# ccam.net
KiCad netlist of a schematic drawn in EAGLE
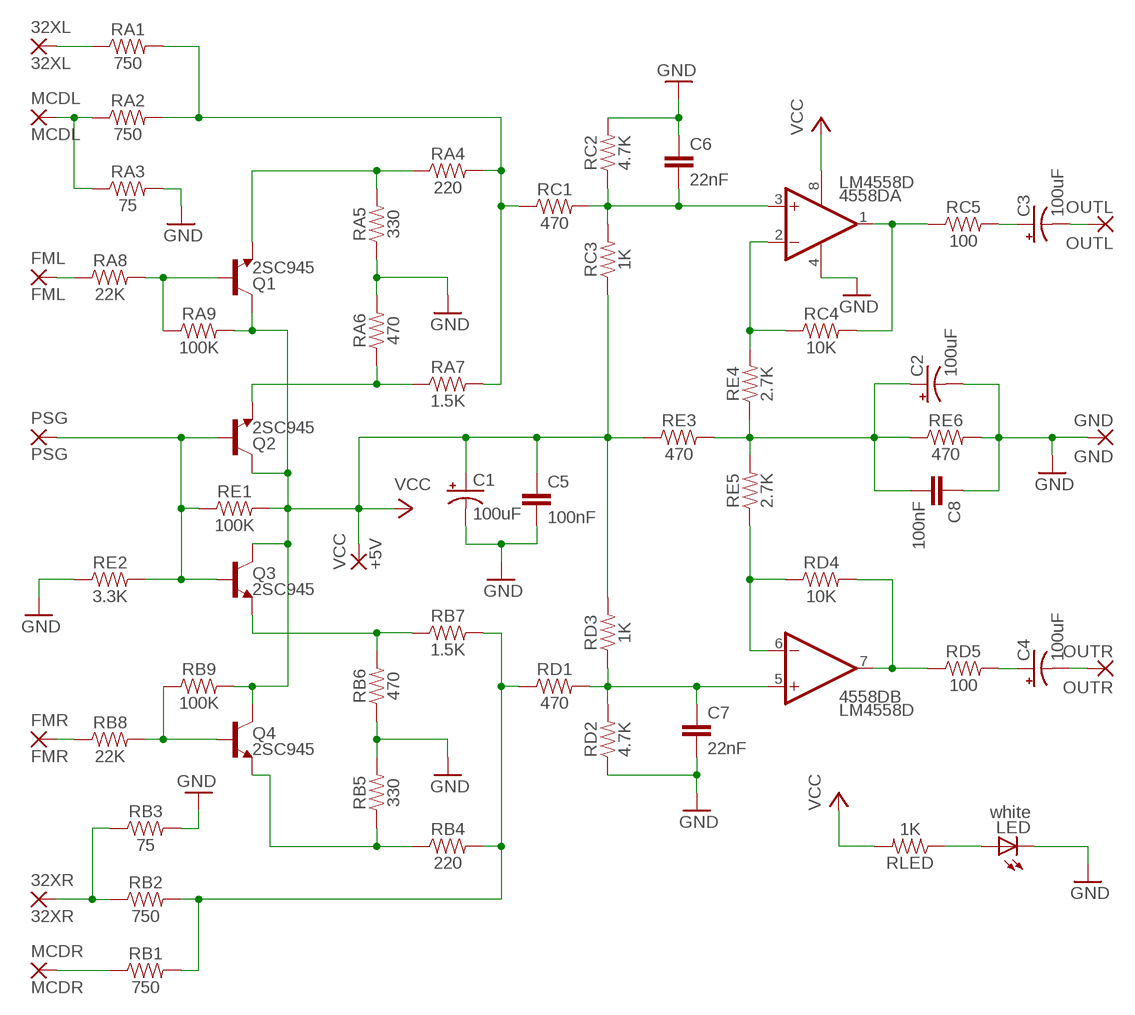
[diagram p0: schematic, sheet 1]

(export (version "E")
  (design (tool "Eeschema 10.0.6"))
  (components
    (comp (ref "32XL")
      (value "32XL")
      (footprint "eagle-import:SMD1,27-2,54")
      (libsource (lib "eagle-import") (part "SMD2"))
    )
    (comp (ref "32XR")
      (value "32XR")
      (footprint "eagle-import:SMD1,27-2,54")
      (libsource (lib "eagle-import") (part "SMD2"))
    )
    (comp (ref "4558D")
      (value "LM4558D")
      (footprint "eagle-import:SO08")
      (libsource (lib "eagle-import") (part "4558DLM"))
    )
    (comp (ref "C1")
      (value "100uF")
      (footprint "eagle-import:EIA6032-NOM")
      (libsource (lib "eagle-import") (part "10UF-POLAR-EIA6032-25V-10%"))
    )
    (comp (ref "C2")
      (value "100uF")
      (footprint "eagle-import:EIA6032-NOM")
      (libsource (lib "eagle-import") (part "10UF-POLAR-EIA6032-25V-10%"))
    )
    (comp (ref "C3")
      (value "100uF")
      (footprint "eagle-import:EIA6032-NOM")
      (libsource (lib "eagle-import") (part "10UF-POLAR-EIA6032-25V-10%"))
    )
    (comp (ref "C4")
      (value "100uF")
      (footprint "eagle-import:EIA6032-NOM")
      (libsource (lib "eagle-import") (part "10UF-POLAR-EIA6032-25V-10%"))
    )
    (comp (ref "C5")
      (value "100nF")
      (footprint "eagle-import:0805")
      (libsource (lib "eagle-import") (part "1.0UF-0805-25V-(+80/-20%)"))
    )
    (comp (ref "C6")
      (value "22nF")
      (footprint "eagle-import:0805")
      (libsource (lib "eagle-import") (part "1.0UF-0805-25V-(+80/-20%)"))
    )
    (comp (ref "C7")
      (value "22nF")
      (footprint "eagle-import:0805")
      (libsource (lib "eagle-import") (part "1.0UF-0805-25V-(+80/-20%)"))
    )
    (comp (ref "C8")
      (value "100nF")
      (footprint "eagle-import:0805")
      (libsource (lib "eagle-import") (part "1.0UF-0805-25V-(+80/-20%)"))
    )
    (comp (ref "FML")
      (value "FML")
      (footprint "eagle-import:SMD1,27-2,54")
      (libsource (lib "eagle-import") (part "SMD2"))
    )
    (comp (ref "FMR")
      (value "FMR")
      (footprint "eagle-import:SMD1,27-2,54")
      (libsource (lib "eagle-import") (part "SMD2"))
    )
    (comp (ref "GND")
      (value "GND")
      (footprint "eagle-import:SMD1,27-2,54")
      (libsource (lib "eagle-import") (part "SMD2"))
    )
    (comp (ref "LED")
      (value "white")
      (footprint "eagle-import:CHIP-LED0805")
      (libsource (lib "eagle-import") (part "LEDCHIP-LED0805"))
    )
    (comp (ref "MCDL")
      (value "MCDL")
      (footprint "eagle-import:SMD1,27-2,54")
      (libsource (lib "eagle-import") (part "SMD2"))
    )
    (comp (ref "MCDR")
      (value "MCDR")
      (footprint "eagle-import:SMD1,27-2,54")
      (libsource (lib "eagle-import") (part "SMD2"))
    )
    (comp (ref "OUTL")
      (value "OUTL")
      (footprint "eagle-import:SMD1,27-2,54")
      (libsource (lib "eagle-import") (part "SMD2"))
    )
    (comp (ref "OUTR")
      (value "OUTR")
      (footprint "eagle-import:SMD1,27-2,54")
      (libsource (lib "eagle-import") (part "SMD2"))
    )
    (comp (ref "PSG")
      (value "PSG")
      (footprint "eagle-import:SMD1,27-2,54")
      (libsource (lib "eagle-import") (part "SMD2"))
    )
    (comp (ref "Q1")
      (value "2SC945")
      (footprint "eagle-import:SOT23-3")
      (libsource (lib "eagle-import") (part "TRANS_NPN-MMBT2222AL"))
    )
    (comp (ref "Q2")
      (value "2SC945")
      (footprint "eagle-import:SOT23-3")
      (libsource (lib "eagle-import") (part "TRANS_NPN-MMBT2222AL"))
    )
    (comp (ref "Q3")
      (value "2SC945")
      (footprint "eagle-import:SOT23-3")
      (libsource (lib "eagle-import") (part "TRANS_NPN-MMBT2222AL"))
    )
    (comp (ref "Q4")
      (value "2SC945")
      (footprint "eagle-import:SOT23-3")
      (libsource (lib "eagle-import") (part "TRANS_NPN-MMBT2222AL"))
    )
    (comp (ref "RA1")
      (value "750")
      (footprint "eagle-import:0805")
      (libsource (lib "eagle-import") (part "0.22OHM-0805-1/4W-1%"))
    )
    (comp (ref "RA2")
      (value "750")
      (footprint "eagle-import:0805")
      (libsource (lib "eagle-import") (part "0.22OHM-0805-1/4W-1%"))
    )
    (comp (ref "RA3")
      (value "75")
      (footprint "eagle-import:0805")
      (libsource (lib "eagle-import") (part "0.22OHM-0805-1/4W-1%"))
    )
    (comp (ref "RA4")
      (value "220")
      (footprint "eagle-import:0805")
      (libsource (lib "eagle-import") (part "0.22OHM-0805-1/4W-1%"))
    )
    (comp (ref "RA5")
      (value "330")
      (footprint "eagle-import:0805")
      (libsource (lib "eagle-import") (part "0.22OHM-0805-1/4W-1%"))
    )
    (comp (ref "RA6")
      (value "470")
      (footprint "eagle-import:0805")
      (libsource (lib "eagle-import") (part "0.22OHM-0805-1/4W-1%"))
    )
    (comp (ref "RA7")
      (value "1.5K")
      (footprint "eagle-import:0805")
      (libsource (lib "eagle-import") (part "0.22OHM-0805-1/4W-1%"))
    )
    (comp (ref "RA8")
      (value "22K")
      (footprint "eagle-import:0805")
      (libsource (lib "eagle-import") (part "0.22OHM-0805-1/4W-1%"))
    )
    (comp (ref "RA9")
      (value "100K")
      (footprint "eagle-import:0805")
      (libsource (lib "eagle-import") (part "0.22OHM-0805-1/4W-1%"))
    )
    (comp (ref "RB1")
      (value "750")
      (footprint "eagle-import:0805")
      (libsource (lib "eagle-import") (part "0.22OHM-0805-1/4W-1%"))
    )
    (comp (ref "RB2")
      (value "750")
      (footprint "eagle-import:0805")
      (libsource (lib "eagle-import") (part "0.22OHM-0805-1/4W-1%"))
    )
    (comp (ref "RB3")
      (value "75")
      (footprint "eagle-import:0805")
      (libsource (lib "eagle-import") (part "0.22OHM-0805-1/4W-1%"))
    )
    (comp (ref "RB4")
      (value "220")
      (footprint "eagle-import:0805")
      (libsource (lib "eagle-import") (part "0.22OHM-0805-1/4W-1%"))
    )
    (comp (ref "RB5")
      (value "330")
      (footprint "eagle-import:0805")
      (libsource (lib "eagle-import") (part "0.22OHM-0805-1/4W-1%"))
    )
    (comp (ref "RB6")
      (value "470")
      (footprint "eagle-import:0805")
      (libsource (lib "eagle-import") (part "0.22OHM-0805-1/4W-1%"))
    )
    (comp (ref "RB7")
      (value "1.5K")
      (footprint "eagle-import:0805")
      (libsource (lib "eagle-import") (part "0.22OHM-0805-1/4W-1%"))
    )
    (comp (ref "RB8")
      (value "22K")
      (footprint "eagle-import:0805")
      (libsource (lib "eagle-import") (part "0.22OHM-0805-1/4W-1%"))
    )
    (comp (ref "RB9")
      (value "100K")
      (footprint "eagle-import:0805")
      (libsource (lib "eagle-import") (part "0.22OHM-0805-1/4W-1%"))
    )
    (comp (ref "RC1")
      (value "470")
      (footprint "eagle-import:0805")
      (libsource (lib "eagle-import") (part "0.22OHM-0805-1/4W-1%"))
    )
    (comp (ref "RC2")
      (value "4.7K")
      (footprint "eagle-import:0805")
      (libsource (lib "eagle-import") (part "0.22OHM-0805-1/4W-1%"))
    )
    (comp (ref "RC3")
      (value "1K")
      (footprint "eagle-import:0805")
      (libsource (lib "eagle-import") (part "0.22OHM-0805-1/4W-1%"))
    )
    (comp (ref "RC4")
      (value "10K")
      (footprint "eagle-import:0805")
      (libsource (lib "eagle-import") (part "0.22OHM-0805-1/4W-1%"))
    )
    (comp (ref "RC5")
      (value "100")
      (footprint "eagle-import:0805")
      (libsource (lib "eagle-import") (part "0.22OHM-0805-1/4W-1%"))
    )
    (comp (ref "RD1")
      (value "470")
      (footprint "eagle-import:0805")
      (libsource (lib "eagle-import") (part "0.22OHM-0805-1/4W-1%"))
    )
    (comp (ref "RD2")
      (value "4.7K")
      (footprint "eagle-import:0805")
      (libsource (lib "eagle-import") (part "0.22OHM-0805-1/4W-1%"))
    )
    (comp (ref "RD3")
      (value "1K")
      (footprint "eagle-import:0805")
      (libsource (lib "eagle-import") (part "0.22OHM-0805-1/4W-1%"))
    )
    (comp (ref "RD4")
      (value "10K")
      (footprint "eagle-import:0805")
      (libsource (lib "eagle-import") (part "0.22OHM-0805-1/4W-1%"))
    )
    (comp (ref "RD5")
      (value "100")
      (footprint "eagle-import:0805")
      (libsource (lib "eagle-import") (part "0.22OHM-0805-1/4W-1%"))
    )
    (comp (ref "RE1")
      (value "100K")
      (footprint "eagle-import:0805")
      (libsource (lib "eagle-import") (part "0.22OHM-0805-1/4W-1%"))
    )
    (comp (ref "RE2")
      (value "3.3K")
      (footprint "eagle-import:0805")
      (libsource (lib "eagle-import") (part "0.22OHM-0805-1/4W-1%"))
    )
    (comp (ref "RE3")
      (value "470")
      (footprint "eagle-import:0805")
      (libsource (lib "eagle-import") (part "0.22OHM-0805-1/4W-1%"))
    )
    (comp (ref "RE4")
      (value "2.7K")
      (footprint "eagle-import:0805")
      (libsource (lib "eagle-import") (part "0.22OHM-0805-1/4W-1%"))
    )
    (comp (ref "RE5")
      (value "2.7K")
      (footprint "eagle-import:0805")
      (libsource (lib "eagle-import") (part "0.22OHM-0805-1/4W-1%"))
    )
    (comp (ref "RE6")
      (value "470")
      (footprint "eagle-import:0805")
      (libsource (lib "eagle-import") (part "0.22OHM-0805-1/4W-1%"))
    )
    (comp (ref "RLED")
      (value "1K")
      (footprint "eagle-import:0805")
      (libsource (lib "eagle-import") (part "0.22OHM-0805-1/4W-1%"))
    )
    (comp (ref "VCC")
      (value "+5V")
      (footprint "eagle-import:SMD1,27-2,54")
      (libsource (lib "eagle-import") (part "SMD2"))
    )
  )
  (nets
    (net (code "1") (name "GND") (class "Default")
      (node (ref "4558D") (pin "4") (pinfunction "V-_4") (pintype "power_in"))
      (node (ref "C1") (pin "C") (pinfunction "-_C") (pintype "passive"))
      (node (ref "C2") (pin "C") (pinfunction "-_C") (pintype "passive"))
      (node (ref "C5") (pin "2") (pinfunction "2_2") (pintype "passive"))
      (node (ref "C6") (pin "1") (pinfunction "1_1") (pintype "passive"))
      (node (ref "C7") (pin "2") (pinfunction "2_2") (pintype "passive"))
      (node (ref "C8") (pin "1") (pinfunction "1_1") (pintype "passive"))
      (node (ref "GND") (pin "1") (pinfunction "P_1") (pintype "passive"))
      (node (ref "LED") (pin "C") (pinfunction "C_C") (pintype "passive"))
      (node (ref "RA3") (pin "2") (pinfunction "2_2") (pintype "passive"))
      (node (ref "RA5") (pin "1") (pinfunction "1_1") (pintype "passive"))
      (node (ref "RA6") (pin "2") (pinfunction "2_2") (pintype "passive"))
      (node (ref "RB3") (pin "2") (pinfunction "2_2") (pintype "passive"))
      (node (ref "RB5") (pin "2") (pinfunction "2_2") (pintype "passive"))
      (node (ref "RB6") (pin "1") (pinfunction "1_1") (pintype "passive"))
      (node (ref "RC2") (pin "2") (pinfunction "2_2") (pintype "passive"))
      (node (ref "RD2") (pin "1") (pinfunction "1_1") (pintype "passive"))
      (node (ref "RE2") (pin "1") (pinfunction "1_1") (pintype "passive"))
      (node (ref "RE6") (pin "2") (pinfunction "2_2") (pintype "passive"))
    )
    (net (code "2") (name "Net-(32XL-P)") (class "Default")
      (node (ref "32XL") (pin "1") (pinfunction "P_1") (pintype "passive"))
      (node (ref "RA1") (pin "1") (pinfunction "1_1") (pintype "passive"))
    )
    (net (code "3") (name "Net-(32XR-P)") (class "Default")
      (node (ref "32XR") (pin "1") (pinfunction "P_1") (pintype "passive"))
      (node (ref "RB2") (pin "1") (pinfunction "1_1") (pintype "passive"))
      (node (ref "RB3") (pin "1") (pinfunction "1_1") (pintype "passive"))
    )
    (net (code "4") (name "Net-(4558DA-+IN)") (class "Default")
      (node (ref "4558D") (pin "3") (pinfunction "+IN_3") (pintype "input"))
      (node (ref "C6") (pin "2") (pinfunction "2_2") (pintype "passive"))
      (node (ref "RC1") (pin "2") (pinfunction "2_2") (pintype "passive"))
      (node (ref "RC2") (pin "1") (pinfunction "1_1") (pintype "passive"))
      (node (ref "RC3") (pin "2") (pinfunction "2_2") (pintype "passive"))
    )
    (net (code "5") (name "Net-(4558DA--IN)") (class "Default")
      (node (ref "4558D") (pin "2") (pinfunction "-IN_2") (pintype "input"))
      (node (ref "RC4") (pin "1") (pinfunction "1_1") (pintype "passive"))
      (node (ref "RE4") (pin "2") (pinfunction "2_2") (pintype "passive"))
    )
    (net (code "6") (name "Net-(4558DA-OUT)") (class "Default")
      (node (ref "4558D") (pin "1") (pinfunction "OUT_1") (pintype "output"))
      (node (ref "RC4") (pin "2") (pinfunction "2_2") (pintype "passive"))
      (node (ref "RC5") (pin "1") (pinfunction "1_1") (pintype "passive"))
    )
    (net (code "7") (name "Net-(4558DB-+IN)") (class "Default")
      (node (ref "4558D") (pin "5") (pinfunction "+IN_5") (pintype "input"))
      (node (ref "C7") (pin "1") (pinfunction "1_1") (pintype "passive"))
      (node (ref "RD1") (pin "2") (pinfunction "2_2") (pintype "passive"))
      (node (ref "RD2") (pin "2") (pinfunction "2_2") (pintype "passive"))
      (node (ref "RD3") (pin "1") (pinfunction "1_1") (pintype "passive"))
    )
    (net (code "8") (name "Net-(4558DB--IN)") (class "Default")
      (node (ref "4558D") (pin "6") (pinfunction "-IN_6") (pintype "input"))
      (node (ref "RD4") (pin "1") (pinfunction "1_1") (pintype "passive"))
      (node (ref "RE5") (pin "1") (pinfunction "1_1") (pintype "passive"))
    )
    (net (code "9") (name "Net-(4558DB-OUT)") (class "Default")
      (node (ref "4558D") (pin "7") (pinfunction "OUT_7") (pintype "output"))
      (node (ref "RD4") (pin "2") (pinfunction "2_2") (pintype "passive"))
      (node (ref "RD5") (pin "1") (pinfunction "1_1") (pintype "passive"))
    )
    (net (code "10") (name "Net-(C2-+)") (class "Default")
      (node (ref "C2") (pin "A") (pinfunction "+_A") (pintype "passive"))
      (node (ref "C8") (pin "2") (pinfunction "2_2") (pintype "passive"))
      (node (ref "RE3") (pin "2") (pinfunction "2_2") (pintype "passive"))
      (node (ref "RE4") (pin "1") (pinfunction "1_1") (pintype "passive"))
      (node (ref "RE5") (pin "2") (pinfunction "2_2") (pintype "passive"))
      (node (ref "RE6") (pin "1") (pinfunction "1_1") (pintype "passive"))
    )
    (net (code "11") (name "Net-(C3-+)") (class "Default")
      (node (ref "C3") (pin "A") (pinfunction "+_A") (pintype "passive"))
      (node (ref "RC5") (pin "2") (pinfunction "2_2") (pintype "passive"))
    )
    (net (code "12") (name "Net-(C3--)") (class "Default")
      (node (ref "C3") (pin "C") (pinfunction "-_C") (pintype "passive"))
      (node (ref "OUTL") (pin "1") (pinfunction "P_1") (pintype "passive"))
    )
    (net (code "13") (name "Net-(C4-+)") (class "Default")
      (node (ref "C4") (pin "A") (pinfunction "+_A") (pintype "passive"))
      (node (ref "RD5") (pin "2") (pinfunction "2_2") (pintype "passive"))
    )
    (net (code "14") (name "Net-(C4--)") (class "Default")
      (node (ref "C4") (pin "C") (pinfunction "-_C") (pintype "passive"))
      (node (ref "OUTR") (pin "1") (pinfunction "P_1") (pintype "passive"))
    )
    (net (code "15") (name "Net-(FML-P)") (class "Default")
      (node (ref "FML") (pin "1") (pinfunction "P_1") (pintype "passive"))
      (node (ref "RA8") (pin "1") (pinfunction "1_1") (pintype "passive"))
    )
    (net (code "16") (name "Net-(FMR-P)") (class "Default")
      (node (ref "FMR") (pin "1") (pinfunction "P_1") (pintype "passive"))
      (node (ref "RB8") (pin "1") (pinfunction "1_1") (pintype "passive"))
    )
    (net (code "17") (name "Net-(LED-PadA)") (class "Default")
      (node (ref "LED") (pin "A") (pinfunction "A_A") (pintype "passive"))
      (node (ref "RLED") (pin "1") (pinfunction "1_1") (pintype "passive"))
    )
    (net (code "18") (name "Net-(MCDL-P)") (class "Default")
      (node (ref "MCDL") (pin "1") (pinfunction "P_1") (pintype "passive"))
      (node (ref "RA2") (pin "1") (pinfunction "1_1") (pintype "passive"))
      (node (ref "RA3") (pin "1") (pinfunction "1_1") (pintype "passive"))
    )
    (net (code "19") (name "Net-(MCDR-P)") (class "Default")
      (node (ref "MCDR") (pin "1") (pinfunction "P_1") (pintype "passive"))
      (node (ref "RB1") (pin "1") (pinfunction "1_1") (pintype "passive"))
    )
    (net (code "20") (name "Net-(PSG-P)") (class "Default")
      (node (ref "PSG") (pin "1") (pinfunction "P_1") (pintype "passive"))
      (node (ref "Q2") (pin "1") (pinfunction "B_1") (pintype "passive"))
      (node (ref "Q3") (pin "1") (pinfunction "B_1") (pintype "passive"))
      (node (ref "RE1") (pin "1") (pinfunction "1_1") (pintype "passive"))
      (node (ref "RE2") (pin "2") (pinfunction "2_2") (pintype "passive"))
    )
    (net (code "21") (name "Net-(Q1-B)") (class "Default")
      (node (ref "Q1") (pin "1") (pinfunction "B_1") (pintype "passive"))
      (node (ref "RA8") (pin "2") (pinfunction "2_2") (pintype "passive"))
      (node (ref "RA9") (pin "1") (pinfunction "1_1") (pintype "passive"))
    )
    (net (code "22") (name "Net-(Q1-E)") (class "Default")
      (node (ref "Q1") (pin "2") (pinfunction "E_2") (pintype "passive"))
      (node (ref "RA4") (pin "1") (pinfunction "1_1") (pintype "passive"))
      (node (ref "RA5") (pin "2") (pinfunction "2_2") (pintype "passive"))
    )
    (net (code "23") (name "Net-(Q2-E)") (class "Default")
      (node (ref "Q2") (pin "2") (pinfunction "E_2") (pintype "passive"))
      (node (ref "RA6") (pin "1") (pinfunction "1_1") (pintype "passive"))
      (node (ref "RA7") (pin "1") (pinfunction "1_1") (pintype "passive"))
    )
    (net (code "24") (name "Net-(Q3-E)") (class "Default")
      (node (ref "Q3") (pin "2") (pinfunction "E_2") (pintype "passive"))
      (node (ref "RB6") (pin "2") (pinfunction "2_2") (pintype "passive"))
      (node (ref "RB7") (pin "1") (pinfunction "1_1") (pintype "passive"))
    )
    (net (code "25") (name "Net-(Q4-B)") (class "Default")
      (node (ref "Q4") (pin "1") (pinfunction "B_1") (pintype "passive"))
      (node (ref "RB8") (pin "2") (pinfunction "2_2") (pintype "passive"))
      (node (ref "RB9") (pin "1") (pinfunction "1_1") (pintype "passive"))
    )
    (net (code "26") (name "Net-(Q4-E)") (class "Default")
      (node (ref "Q4") (pin "2") (pinfunction "E_2") (pintype "passive"))
      (node (ref "RB4") (pin "1") (pinfunction "1_1") (pintype "passive"))
      (node (ref "RB5") (pin "1") (pinfunction "1_1") (pintype "passive"))
    )
    (net (code "27") (name "Net-(RA1-Pad2)") (class "Default")
      (node (ref "RA1") (pin "2") (pinfunction "2_2") (pintype "passive"))
      (node (ref "RA2") (pin "2") (pinfunction "2_2") (pintype "passive"))
      (node (ref "RA4") (pin "2") (pinfunction "2_2") (pintype "passive"))
      (node (ref "RA7") (pin "2") (pinfunction "2_2") (pintype "passive"))
      (node (ref "RC1") (pin "1") (pinfunction "1_1") (pintype "passive"))
    )
    (net (code "28") (name "Net-(RB1-Pad2)") (class "Default")
      (node (ref "RB1") (pin "2") (pinfunction "2_2") (pintype "passive"))
      (node (ref "RB2") (pin "2") (pinfunction "2_2") (pintype "passive"))
      (node (ref "RB4") (pin "2") (pinfunction "2_2") (pintype "passive"))
      (node (ref "RB7") (pin "2") (pinfunction "2_2") (pintype "passive"))
      (node (ref "RD1") (pin "1") (pinfunction "1_1") (pintype "passive"))
    )
    (net (code "29") (name "VCC") (class "Default")
      (node (ref "4558D") (pin "8") (pinfunction "V+_8") (pintype "power_in"))
      (node (ref "C1") (pin "A") (pinfunction "+_A") (pintype "passive"))
      (node (ref "C5") (pin "1") (pinfunction "1_1") (pintype "passive"))
      (node (ref "Q1") (pin "3") (pinfunction "C_3") (pintype "passive"))
      (node (ref "Q2") (pin "3") (pinfunction "C_3") (pintype "passive"))
      (node (ref "Q3") (pin "3") (pinfunction "C_3") (pintype "passive"))
      (node (ref "Q4") (pin "3") (pinfunction "C_3") (pintype "passive"))
      (node (ref "RA9") (pin "2") (pinfunction "2_2") (pintype "passive"))
      (node (ref "RB9") (pin "2") (pinfunction "2_2") (pintype "passive"))
      (node (ref "RC3") (pin "1") (pinfunction "1_1") (pintype "passive"))
      (node (ref "RD3") (pin "2") (pinfunction "2_2") (pintype "passive"))
      (node (ref "RE1") (pin "2") (pinfunction "2_2") (pintype "passive"))
      (node (ref "RE3") (pin "1") (pinfunction "1_1") (pintype "passive"))
      (node (ref "RLED") (pin "2") (pinfunction "2_2") (pintype "passive"))
      (node (ref "VCC") (pin "1") (pinfunction "P_1") (pintype "passive"))
    )
  )
)
